# Ethernet.net
KiCad netlist of a schematic drawn in Altium Designer
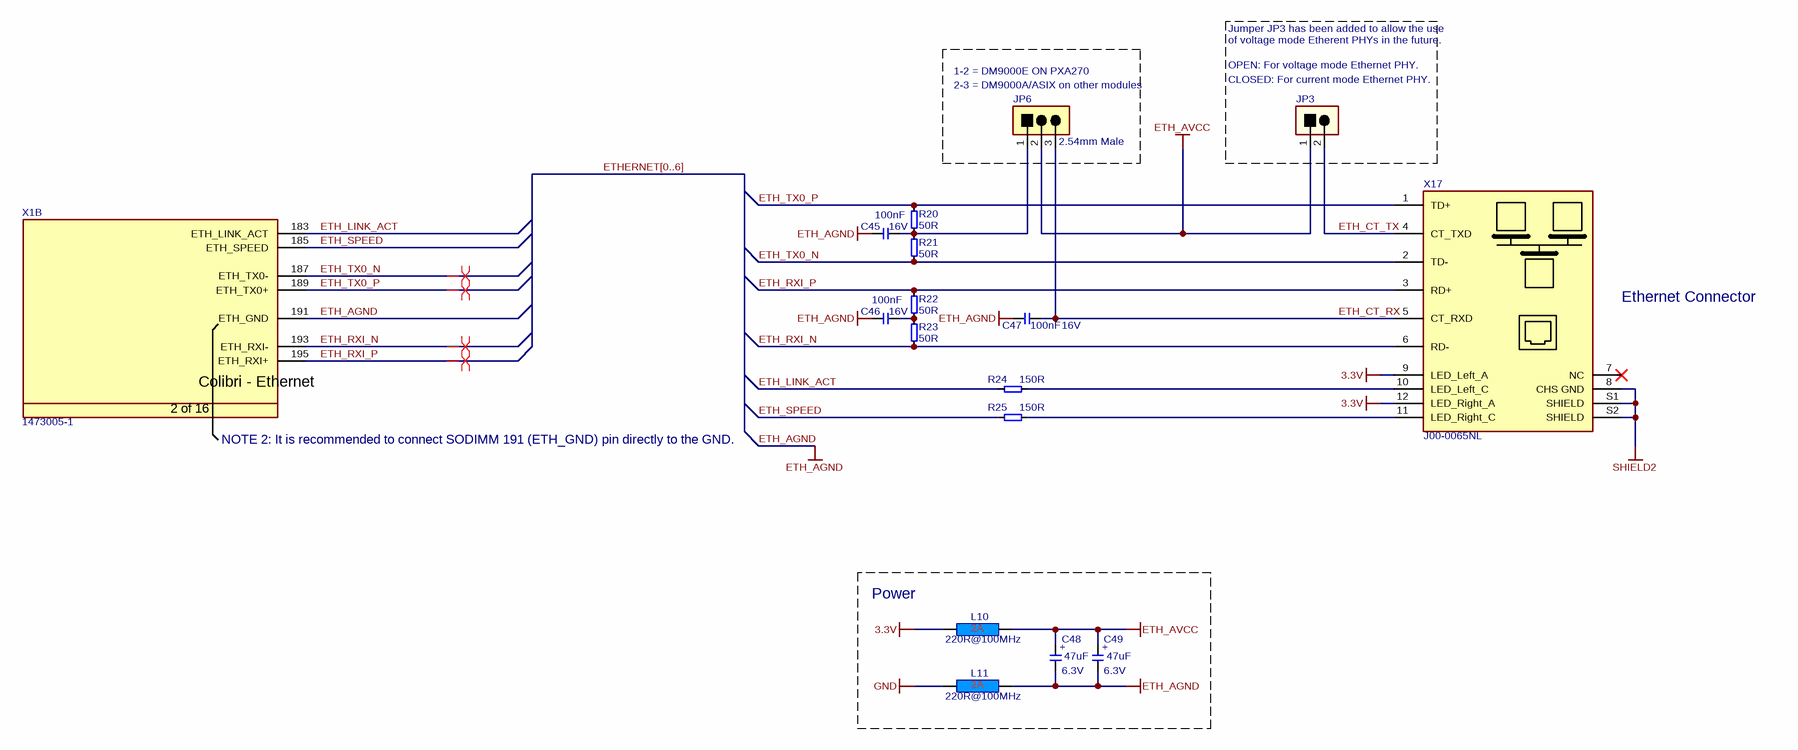
[diagram p0: Ethernet.SchDoc]

(export (version "E")
  (design (tool "Eeschema 10.0.6"))
  (components
    (comp (ref "C45")
      (value "100nF")
      (footprint "T_CAPC0603X33N")
      (description "Capacitor Ceramic X7R 100nF 16V 10% 0603")
      (fields (field (name "TOLERANCE") "10%") (field (name "RATING") "16V"))
      (libsource (lib "Evaluation Board") (part "C-X7R-100nF-16V-10%-0603"))
    )
    (comp (ref "C46")
      (value "100nF")
      (footprint "T_CAPC0603X33N")
      (description "Capacitor Ceramic X7R 100nF 16V 10% 0603")
      (fields (field (name "TOLERANCE") "10%") (field (name "RATING") "16V"))
      (libsource (lib "Evaluation Board") (part "C-X7R-100nF-16V-10%-0603"))
    )
    (comp (ref "C47")
      (value "100nF")
      (footprint "T_CAPC0603X33N")
      (description "Capacitor Ceramic X7R 100nF 16V 10% 0603")
      (fields (field (name "TOLERANCE") "10%") (field (name "RATING") "16V"))
      (libsource (lib "Evaluation Board") (part "C-X7R-100nF-16V-10%-0603"))
    )
    (comp (ref "C48")
      (value "47uF")
      (footprint "CAPMP3528X210N")
      (description "Capacitor TA 47uF 6.3V 20% 3216")
      (fields (field (name "TOLERANCE") "20%") (field (name "RATING") "6.3V"))
      (libsource (lib "Evaluation Board") (part "C-TA-47uF-6.3V-20%-3216"))
    )
    (comp (ref "C49")
      (value "47uF")
      (footprint "CAPMP3528X210N")
      (description "Capacitor TA 47uF 6.3V 20% 3216")
      (fields (field (name "TOLERANCE") "20%") (field (name "RATING") "6.3V"))
      (libsource (lib "") (part "C-TA-47uF-6.3V-20%-3216_1"))
    )
    (comp (ref "JP3")
      (value "TSW-101-07-G-D")
      (footprint "T_Samtec_TSW-101-07-G-D")
      (description "Header male, 1x2 Pins, 2.54 mm pitch")
      (libsource (lib "Evaluation Board") (part "CON-Samtec-TSW-101-07-G-D"))
    )
    (comp (ref "JP6")
      (value "826936-3")
      (footprint "T_TYCO_826936-3")
      (description "Jumper, 3-Pin")
      (libsource (lib "Evaluation Board") (part "CON-Tyco-826936-3-1X3-2.54mm-JP"))
    )
    (comp (ref "L10")
      (value "220R@100MHz")
      (footprint "INDC1608X95N")
      (description "220R@100MHz 2A EMI FILTER")
      (fields (field (name "TOLERANCE") "25%"))
      (libsource (lib "Evaluation Board") (part "L-220R@100MHz-2A-25%-0603"))
    )
    (comp (ref "L11")
      (value "220R@100MHz")
      (footprint "INDC1608X95N")
      (description "220R@100MHz 2A EMI FILTER")
      (fields (field (name "TOLERANCE") "25%"))
      (libsource (lib "Evaluation Board") (part "L-220R@100MHz-2A-25%-0603"))
    )
    (comp (ref "R20")
      (value "50R")
      (footprint "t_RESC0603X30N")
      (description "Resistor 50 ohm 63mW 1% 0603")
      (fields (field (name "TOLERANCE") "1%"))
      (libsource (lib "Evaluation Board") (part "R-50R-63mW-1%-0603"))
    )
    (comp (ref "R21")
      (value "50R")
      (footprint "t_RESC0603X30N")
      (description "Resistor 50 ohm 63mW 1% 0603")
      (fields (field (name "TOLERANCE") "1%"))
      (libsource (lib "Evaluation Board") (part "R-50R-63mW-1%-0603"))
    )
    (comp (ref "R22")
      (value "50R")
      (footprint "t_RESC0603X30N")
      (description "Resistor 50 ohm 63mW 1% 0603")
      (fields (field (name "TOLERANCE") "1%"))
      (libsource (lib "Evaluation Board") (part "R-50R-63mW-1%-0603"))
    )
    (comp (ref "R23")
      (value "50R")
      (footprint "t_RESC0603X30N")
      (description "Resistor 50 ohm 63mW 1% 0603")
      (fields (field (name "TOLERANCE") "1%"))
      (libsource (lib "Evaluation Board") (part "R-50R-63mW-1%-0603"))
    )
    (comp (ref "R24")
      (value "150R")
      (footprint "t_RESC0603X30N")
      (description "Resistor 150 ohm 63mW 1% 0603")
      (fields (field (name "TOLERANCE") "1%"))
      (libsource (lib "Evaluation Board") (part "R-150R-63mW-1%-0603"))
    )
    (comp (ref "R25")
      (value "150R")
      (footprint "t_RESC0603X30N")
      (description "Resistor 150 ohm 63mW 1% 0603")
      (fields (field (name "TOLERANCE") "1%"))
      (libsource (lib "Evaluation Board") (part "R-150R-63mW-1%-0603"))
    )
    (comp (ref "X1")
      (value "CON-Tyco-1473005-1-200-0.6mm")
      (footprint "T_Tyco_1473005-1")
      (description "SODIMM Connector")
      (fields (field (name "MANUFACTURER PART NO.") "1473005-1"))
      (libsource (lib "Evaluation Board") (part "CON-Tyco-1473005-1-200-0.6mm"))
    )
    (comp (ref "X17")
      (value "J00-0065NL")
      (footprint "T_Pulse_J00-0065NL")
      (description "RJ45 Connector")
      (fields (field (name "MANUFACTURER PART NO.") "J00-0065NL"))
      (libsource (lib "Evaluation Board") (part "CON-Pulse-J00-0065NL"))
    )
  )
  (nets
    (net (code "9") (name "/ETH_CT_RX") (class "Default")
      (node (ref "C47") (pin "2") (pinfunction "2_2") (pintype "passive"))
      (node (ref "JP6") (pin "3") (pinfunction "3_3") (pintype "passive"))
      (node (ref "X17") (pin "5") (pinfunction "CT_RXD_5") (pintype "passive"))
    )
    (net (code "10") (name "/ETH_CT_TX") (class "Default")
      (node (ref "JP3") (pin "2") (pinfunction "2_2") (pintype "passive"))
      (node (ref "X17") (pin "4") (pinfunction "CT_TXD_4") (pintype "passive"))
    )
    (net (code "11") (name "/ETH_LINK_ACT") (class "Default")
      (node (ref "R24") (pin "1") (pinfunction "1_1") (pintype "passive"))
      (node (ref "X1") (pin "183") (pinfunction "ETH_LINK_ACT_183") (pintype "passive"))
    )
    (net (code "12") (name "/ETH_RXI_N") (class "Default")
      (node (ref "R23") (pin "1") (pinfunction "1_1") (pintype "passive"))
      (node (ref "X1") (pin "193") (pinfunction "ETH_RXI-_193") (pintype "passive"))
      (node (ref "X17") (pin "6") (pinfunction "RD-_6") (pintype "passive"))
    )
    (net (code "13") (name "/ETH_RXI_P") (class "Default")
      (node (ref "R22") (pin "2") (pinfunction "2_2") (pintype "passive"))
      (node (ref "X1") (pin "195") (pinfunction "ETH_RXI+_195") (pintype "passive"))
      (node (ref "X17") (pin "3") (pinfunction "RD+_3") (pintype "passive"))
    )
    (net (code "14") (name "/ETH_SPEED") (class "Default")
      (node (ref "R25") (pin "1") (pinfunction "1_1") (pintype "passive"))
      (node (ref "X1") (pin "185") (pinfunction "ETH_SPEED_185") (pintype "passive"))
    )
    (net (code "15") (name "/ETH_TX0_N") (class "Default")
      (node (ref "R21") (pin "1") (pinfunction "1_1") (pintype "passive"))
      (node (ref "X1") (pin "187") (pinfunction "ETH_TX0-_187") (pintype "passive"))
      (node (ref "X17") (pin "2") (pinfunction "TD-_2") (pintype "passive"))
    )
    (net (code "16") (name "/ETH_TX0_P") (class "Default")
      (node (ref "R20") (pin "2") (pinfunction "2_2") (pintype "passive"))
      (node (ref "X1") (pin "189") (pinfunction "ETH_TX0+_189") (pintype "passive"))
      (node (ref "X17") (pin "1") (pinfunction "TD+_1") (pintype "passive"))
    )
    (net (code "17") (name "3.3V") (class "Default")
      (node (ref "L10") (pin "1") (pinfunction "1_1") (pintype "passive"))
      (node (ref "X17") (pin "12") (pinfunction "LED_Right_A_12") (pintype "passive"))
      (node (ref "X17") (pin "9") (pinfunction "LED_Left_A_9") (pintype "passive"))
    )
    (net (code "18") (name "ETH_AGND") (class "Default")
      (node (ref "C45") (pin "1") (pinfunction "1_1") (pintype "passive"))
      (node (ref "C46") (pin "1") (pinfunction "1_1") (pintype "passive"))
      (node (ref "C47") (pin "1") (pinfunction "1_1") (pintype "passive"))
      (node (ref "C48") (pin "2") (pinfunction "2_2") (pintype "passive"))
      (node (ref "C49") (pin "2") (pinfunction "2_2") (pintype "passive"))
      (node (ref "L11") (pin "2") (pinfunction "2_2") (pintype "passive"))
      (node (ref "X1") (pin "191") (pinfunction "ETH_GND_191") (pintype "passive"))
    )
    (net (code "19") (name "ETH_AVCC") (class "Default")
      (node (ref "C48") (pin "1") (pinfunction "1_1") (pintype "passive"))
      (node (ref "C49") (pin "1") (pinfunction "1_1") (pintype "passive"))
      (node (ref "JP3") (pin "1") (pinfunction "1_1") (pintype "passive"))
      (node (ref "JP6") (pin "2") (pinfunction "2_2") (pintype "passive"))
      (node (ref "L10") (pin "2") (pinfunction "2_2") (pintype "passive"))
    )
    (net (code "20") (name "GND") (class "Default")
      (node (ref "L11") (pin "1") (pinfunction "1_1") (pintype "passive"))
    )
    (net (code "21") (name "Net-(C45-Pad2)") (class "Default")
      (node (ref "C45") (pin "2") (pinfunction "2_2") (pintype "passive"))
      (node (ref "JP6") (pin "1") (pinfunction "1_1") (pintype "passive"))
      (node (ref "R20") (pin "1") (pinfunction "1_1") (pintype "passive"))
      (node (ref "R21") (pin "2") (pinfunction "2_2") (pintype "passive"))
    )
    (net (code "22") (name "Net-(C46-Pad2)") (class "Default")
      (node (ref "C46") (pin "2") (pinfunction "2_2") (pintype "passive"))
      (node (ref "R22") (pin "1") (pinfunction "1_1") (pintype "passive"))
      (node (ref "R23") (pin "2") (pinfunction "2_2") (pintype "passive"))
    )
    (net (code "23") (name "Net-(X17-LED_Left_C)") (class "Default")
      (node (ref "R24") (pin "2") (pinfunction "2_2") (pintype "passive"))
      (node (ref "X17") (pin "10") (pinfunction "LED_Left_C_10") (pintype "passive"))
    )
    (net (code "24") (name "Net-(X17-LED_Right_C)") (class "Default")
      (node (ref "R25") (pin "2") (pinfunction "2_2") (pintype "passive"))
      (node (ref "X17") (pin "11") (pinfunction "LED_Right_C_11") (pintype "passive"))
    )
    (net (code "25") (name "SHIELD2") (class "Default")
      (node (ref "X17") (pin "8") (pinfunction "CHS_GND_8") (pintype "passive"))
      (node (ref "X17") (pin "S1") (pinfunction "SHIELD_S1") (pintype "passive"))
      (node (ref "X17") (pin "S2") (pinfunction "SHIELD_S2") (pintype "passive"))
    )
    (net (code "26") (name "unconnected-(X17-NC-Pad7)") (class "Default")
      (node (ref "X17") (pin "7") (pinfunction "NC_7") (pintype "passive+no_connect"))
    )
  )
)
